# MicroSD_reg.net
KiCad netlist of a schematic drawn in EAGLE
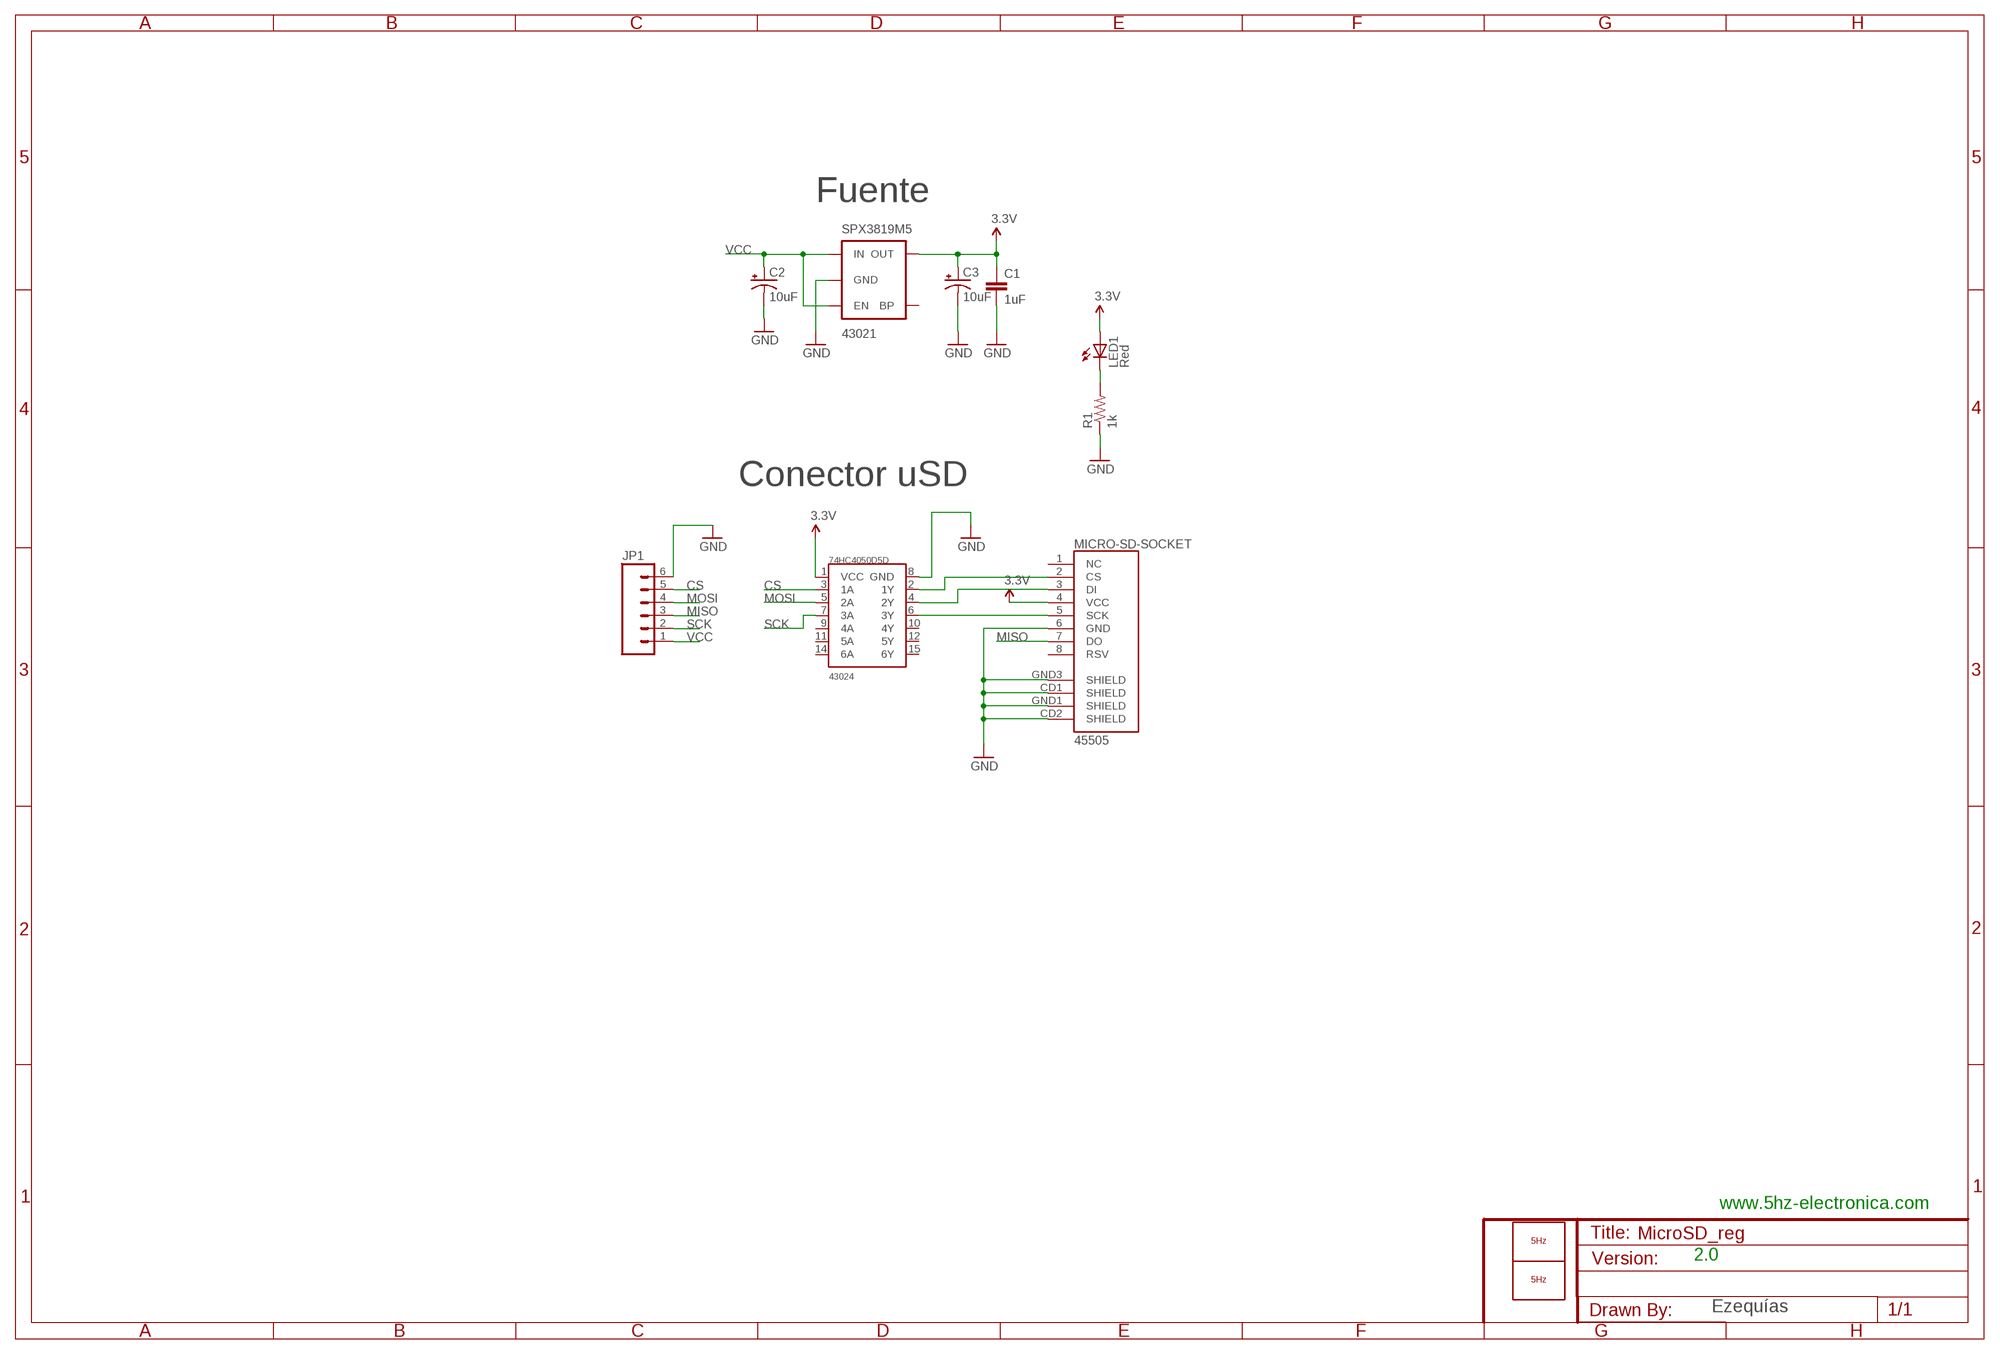
[diagram p0: schematic, sheet 1]

(export (version "E")
  (design (tool "Eeschema 10.0.6"))
  (components
    (comp (ref "74HC4050D5D")
      (value "43024")
      (footprint "eagle-import:SO016")
      (libsource (lib "eagle-import") (part "HEX_CONVERTER"))
    )
    (comp (ref "C1")
      (value "1uF")
      (footprint "eagle-import:0603-CAP")
      (libsource (lib "eagle-import") (part "CAP0603-CAP"))
    )
    (comp (ref "C2")
      (value "10uF")
      (footprint "eagle-import:EIA3216")
      (libsource (lib "eagle-import") (part "CAP_POL1206"))
    )
    (comp (ref "C3")
      (value "10uF")
      (footprint "eagle-import:EIA3216")
      (libsource (lib "eagle-import") (part "CAP_POL1206"))
    )
    (comp (ref "JP1")
      (value "M06SIP")
      (footprint "eagle-import:1X06")
      (libsource (lib "eagle-import") (part "M06SIP"))
    )
    (comp (ref "LED1")
      (value "Red")
      (footprint "eagle-import:LED-0603")
      (libsource (lib "eagle-import") (part "LED0603"))
    )
    (comp (ref "LOGO1")
      (value "LOGO_5HZ_MAIN_10MM")
      (footprint "eagle-import:5HZ_LOGO_MAIN_10MM")
      (libsource (lib "eagle-import") (part "LOGO_5HZ_MAIN_10MM"))
    )
    (comp (ref "LOGO2")
      (value "LOGO_5HZ_CIRC_3MM")
      (footprint "eagle-import:5HZ_LOGO_CIRC_3MM")
      (libsource (lib "eagle-import") (part "LOGO_5HZ_CIRC_3MM"))
    )
    (comp (ref "MICRO-SD-SOCKET")
      (value "45505")
      (footprint "eagle-import:MICRO-SD-SOCKET-PP")
      (libsource (lib "eagle-import") (part "USD-SOCKETNEW"))
    )
    (comp (ref "R1")
      (value "1k")
      (footprint "eagle-import:0603-RES")
      (libsource (lib "eagle-import") (part "RESISTOR0603-RES"))
    )
    (comp (ref "SPX3819M5")
      (value "43021")
      (footprint "eagle-import:SOT23-5")
      (libsource (lib "eagle-import") (part "V_REG_LDOSMD"))
    )
  )
  (nets
    (net (code "1") (name "/CS") (class "Default")
      (node (ref "74HC4050D5D") (pin "3") (pinfunction "1A_3") (pintype "bidirectional"))
      (node (ref "JP1") (pin "5") (pinfunction "5_5") (pintype "passive"))
    )
    (net (code "2") (name "/MISO") (class "Default")
      (node (ref "JP1") (pin "3") (pinfunction "3_3") (pintype "passive"))
      (node (ref "MICRO-SD-SOCKET") (pin "7") (pinfunction "DO_7") (pintype "bidirectional"))
    )
    (net (code "3") (name "/MOSI") (class "Default")
      (node (ref "74HC4050D5D") (pin "5") (pinfunction "2A_5") (pintype "bidirectional"))
      (node (ref "JP1") (pin "4") (pinfunction "4_4") (pintype "passive"))
    )
    (net (code "4") (name "/SCK") (class "Default")
      (node (ref "74HC4050D5D") (pin "7") (pinfunction "3A_7") (pintype "bidirectional"))
      (node (ref "JP1") (pin "2") (pinfunction "2_2") (pintype "passive"))
    )
    (net (code "5") (name "/VCC") (class "Default")
      (node (ref "C2") (pin "A") (pinfunction "+_A") (pintype "passive"))
      (node (ref "JP1") (pin "1") (pinfunction "1_1") (pintype "passive"))
      (node (ref "SPX3819M5") (pin "1") (pinfunction "IN_1") (pintype "input"))
      (node (ref "SPX3819M5") (pin "3") (pinfunction "EN_3") (pintype "input"))
    )
    (net (code "6") (name "3.3V") (class "Default")
      (node (ref "74HC4050D5D") (pin "1") (pinfunction "VCC_1") (pintype "bidirectional"))
      (node (ref "C1") (pin "1") (pinfunction "1_1") (pintype "passive"))
      (node (ref "C3") (pin "A") (pinfunction "+_A") (pintype "passive"))
      (node (ref "LED1") (pin "A") (pinfunction "A_A") (pintype "passive"))
      (node (ref "MICRO-SD-SOCKET") (pin "4") (pinfunction "VCC_4") (pintype "bidirectional"))
      (node (ref "SPX3819M5") (pin "5") (pinfunction "OUT_5") (pintype "passive"))
    )
    (net (code "7") (name "GND") (class "Default")
      (node (ref "74HC4050D5D") (pin "8") (pinfunction "GND_8") (pintype "bidirectional"))
      (node (ref "C1") (pin "2") (pinfunction "2_2") (pintype "passive"))
      (node (ref "C2") (pin "C") (pinfunction "-_C") (pintype "passive"))
      (node (ref "C3") (pin "C") (pinfunction "-_C") (pintype "passive"))
      (node (ref "JP1") (pin "6") (pinfunction "6_6") (pintype "passive"))
      (node (ref "MICRO-SD-SOCKET") (pin "6") (pinfunction "GND_6") (pintype "bidirectional"))
      (node (ref "MICRO-SD-SOCKET") (pin "CD1") (pinfunction "SHIELD_CD1") (pintype "bidirectional"))
      (node (ref "MICRO-SD-SOCKET") (pin "CD2") (pinfunction "SHIELD_CD2") (pintype "bidirectional"))
      (node (ref "MICRO-SD-SOCKET") (pin "GND1") (pinfunction "SHIELD_GND1") (pintype "bidirectional"))
      (node (ref "MICRO-SD-SOCKET") (pin "GND3") (pinfunction "SHIELD_GND3") (pintype "bidirectional"))
      (node (ref "R1") (pin "1") (pinfunction "1_1") (pintype "passive"))
      (node (ref "SPX3819M5") (pin "2") (pinfunction "GND_2") (pintype "input"))
    )
    (net (code "8") (name "Net-(74HC4050D5D-1Y)") (class "Default")
      (node (ref "74HC4050D5D") (pin "2") (pinfunction "1Y_2") (pintype "bidirectional"))
      (node (ref "MICRO-SD-SOCKET") (pin "2") (pinfunction "CS_2") (pintype "bidirectional"))
    )
    (net (code "9") (name "Net-(74HC4050D5D-2Y)") (class "Default")
      (node (ref "74HC4050D5D") (pin "4") (pinfunction "2Y_4") (pintype "bidirectional"))
      (node (ref "MICRO-SD-SOCKET") (pin "3") (pinfunction "DI_3") (pintype "bidirectional"))
    )
    (net (code "10") (name "Net-(74HC4050D5D-3Y)") (class "Default")
      (node (ref "74HC4050D5D") (pin "6") (pinfunction "3Y_6") (pintype "bidirectional"))
      (node (ref "MICRO-SD-SOCKET") (pin "5") (pinfunction "SCK_5") (pintype "bidirectional"))
    )
    (net (code "11") (name "Net-(LED1-PadC)") (class "Default")
      (node (ref "LED1") (pin "C") (pinfunction "C_C") (pintype "passive"))
      (node (ref "R1") (pin "2") (pinfunction "2_2") (pintype "passive"))
    )
    (net (code "12") (name "unconnected-(74HC4050D5D-4A-Pad9)") (class "Default")
      (node (ref "74HC4050D5D") (pin "9") (pinfunction "4A_9") (pintype "bidirectional"))
    )
    (net (code "13") (name "unconnected-(74HC4050D5D-4Y-Pad10)") (class "Default")
      (node (ref "74HC4050D5D") (pin "10") (pinfunction "4Y_10") (pintype "bidirectional"))
    )
    (net (code "14") (name "unconnected-(74HC4050D5D-5A-Pad11)") (class "Default")
      (node (ref "74HC4050D5D") (pin "11") (pinfunction "5A_11") (pintype "bidirectional"))
    )
    (net (code "15") (name "unconnected-(74HC4050D5D-5Y-Pad12)") (class "Default")
      (node (ref "74HC4050D5D") (pin "12") (pinfunction "5Y_12") (pintype "bidirectional"))
    )
    (net (code "16") (name "unconnected-(74HC4050D5D-6A-Pad14)") (class "Default")
      (node (ref "74HC4050D5D") (pin "14") (pinfunction "6A_14") (pintype "bidirectional"))
    )
    (net (code "17") (name "unconnected-(74HC4050D5D-6Y-Pad15)") (class "Default")
      (node (ref "74HC4050D5D") (pin "15") (pinfunction "6Y_15") (pintype "bidirectional"))
    )
    (net (code "18") (name "unconnected-(MICRO-SD-SOCKET-NC-Pad1)") (class "Default")
      (node (ref "MICRO-SD-SOCKET") (pin "1") (pinfunction "NC_1") (pintype "bidirectional"))
    )
    (net (code "19") (name "unconnected-(MICRO-SD-SOCKET-RSV-Pad8)") (class "Default")
      (node (ref "MICRO-SD-SOCKET") (pin "8") (pinfunction "RSV_8") (pintype "bidirectional"))
    )
    (net (code "20") (name "unconnected-(SPX3819M5-BP-Pad4)") (class "Default")
      (node (ref "SPX3819M5") (pin "4") (pinfunction "BP_4") (pintype "input"))
    )
  )
)
